# CLKB_SMI_if_1_6.net
KiCad netlist of a schematic drawn in Altium Designer
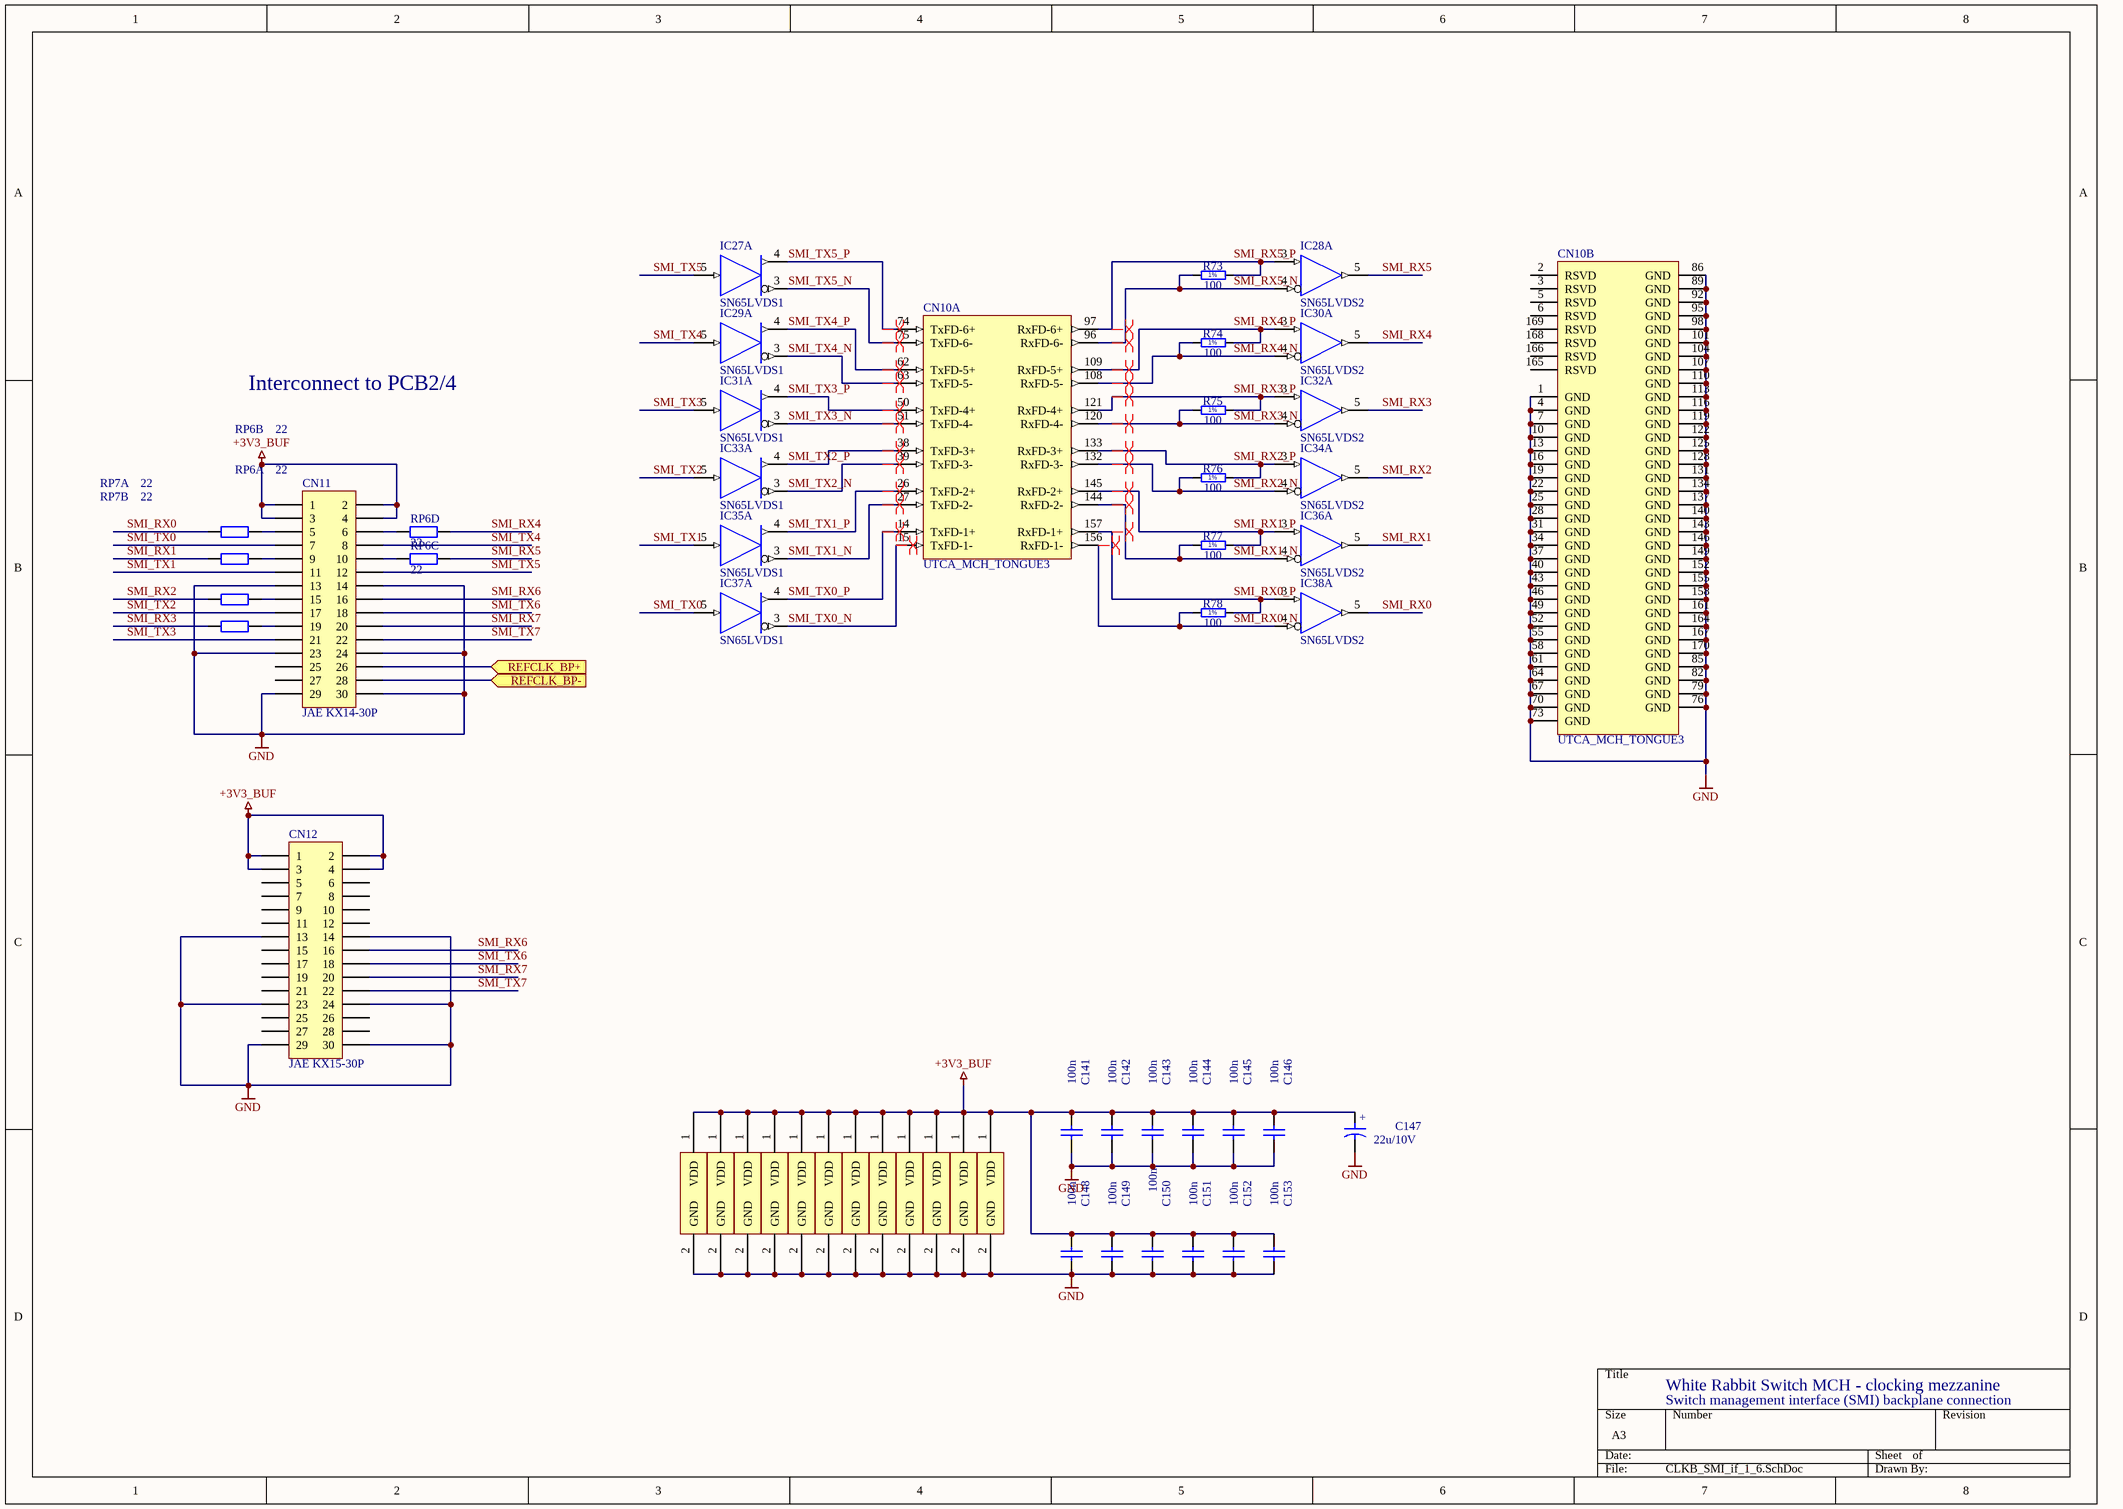
[diagram p0: CLKB_SMI_if_1_6.SchDoc]

(export (version "E")
  (design (tool "Eeschema 10.0.6"))
  (components
    (comp (ref "C141")
      (value "100n")
      (footprint "CAPC1608X87N")
      (description "Non-polarised capacitor")
      (fields
        (field (name "PART NUMBER") "CC0603_100NF_50V_10%_X7R")
        (field (name "VOLTAGE") "50V")
        (field (name "AUTHOR") "CERN DEM JLC")
      )
      (libsource (lib "Capacitors") (part "Capacitor - non polarized"))
    )
    (comp (ref "C142")
      (value "100n")
      (footprint "CAPC1608X87N")
      (description "Non-polarised capacitor")
      (fields
        (field (name "PART NUMBER") "CC0603_100NF_50V_10%_X7R")
        (field (name "VOLTAGE") "50V")
        (field (name "AUTHOR") "CERN DEM JLC")
      )
      (libsource (lib "Capacitors") (part "Capacitor - non polarized"))
    )
    (comp (ref "C143")
      (value "100n")
      (footprint "CAPC1608X87N")
      (description "Non-polarised capacitor")
      (fields
        (field (name "PART NUMBER") "CC0603_100NF_50V_10%_X7R")
        (field (name "VOLTAGE") "50V")
        (field (name "AUTHOR") "CERN DEM JLC")
      )
      (libsource (lib "Capacitors") (part "Capacitor - non polarized"))
    )
    (comp (ref "C144")
      (value "100n")
      (footprint "CAPC1608X87N")
      (description "Non-polarised capacitor")
      (fields
        (field (name "PART NUMBER") "CC0603_100NF_50V_10%_X7R")
        (field (name "VOLTAGE") "50V")
        (field (name "AUTHOR") "CERN DEM JLC")
      )
      (libsource (lib "Capacitors") (part "Capacitor - non polarized"))
    )
    (comp (ref "C145")
      (value "100n")
      (footprint "CAPC1608X87N")
      (description "Non-polarised capacitor")
      (fields
        (field (name "PART NUMBER") "CC0603_100NF_50V_10%_X7R")
        (field (name "VOLTAGE") "50V")
        (field (name "AUTHOR") "CERN DEM JLC")
      )
      (libsource (lib "Capacitors") (part "Capacitor - non polarized"))
    )
    (comp (ref "C146")
      (value "100n")
      (footprint "CAPC1608X87N")
      (description "Non-polarised capacitor")
      (fields
        (field (name "PART NUMBER") "CC0603_100NF_50V_10%_X7R")
        (field (name "VOLTAGE") "50V")
        (field (name "AUTHOR") "CERN DEM JLC")
      )
      (libsource (lib "Capacitors") (part "Capacitor - non polarized"))
    )
    (comp (ref "C147")
      (value "22u/10V")
      (footprint "CAPMP3216X180N")
      (description "Polarised capacitor")
      (fields
        (field (name "PART NUMBER") "CTE3216-18_22UF_10V_10%")
        (field (name "VOLTAGE") "10V")
        (field (name "AUTHOR") "CERN DEM JLC")
      )
      (libsource (lib "Capacitors") (part "Capacitor - polarized"))
    )
    (comp (ref "C148")
      (value "100n")
      (footprint "CAPC1608X87N")
      (description "Non-polarised capacitor")
      (fields
        (field (name "PART NUMBER") "CC0603_100NF_50V_10%_X7R")
        (field (name "VOLTAGE") "50V")
        (field (name "AUTHOR") "CERN DEM JLC")
      )
      (libsource (lib "Capacitors") (part "Capacitor - non polarized"))
    )
    (comp (ref "C149")
      (value "100n")
      (footprint "CAPC1608X87N")
      (description "Non-polarised capacitor")
      (fields
        (field (name "PART NUMBER") "CC0603_100NF_50V_10%_X7R")
        (field (name "VOLTAGE") "50V")
        (field (name "AUTHOR") "CERN DEM JLC")
      )
      (libsource (lib "Capacitors") (part "Capacitor - non polarized"))
    )
    (comp (ref "C150")
      (value "100n")
      (footprint "CAPC1608X87N")
      (description "Non-polarised capacitor")
      (fields
        (field (name "PART NUMBER") "CC0603_100NF_50V_10%_X7R")
        (field (name "VOLTAGE") "50V")
        (field (name "AUTHOR") "CERN DEM JLC")
      )
      (libsource (lib "Capacitors") (part "Capacitor - non polarized"))
    )
    (comp (ref "C151")
      (value "100n")
      (footprint "CAPC1608X87N")
      (description "Non-polarised capacitor")
      (fields
        (field (name "PART NUMBER") "CC0603_100NF_50V_10%_X7R")
        (field (name "VOLTAGE") "50V")
        (field (name "AUTHOR") "CERN DEM JLC")
      )
      (libsource (lib "Capacitors") (part "Capacitor - non polarized"))
    )
    (comp (ref "C152")
      (value "100n")
      (footprint "CAPC1608X87N")
      (description "Non-polarised capacitor")
      (fields
        (field (name "PART NUMBER") "CC0603_100NF_50V_10%_X7R")
        (field (name "VOLTAGE") "50V")
        (field (name "AUTHOR") "CERN DEM JLC")
      )
      (libsource (lib "Capacitors") (part "Capacitor - non polarized"))
    )
    (comp (ref "C153")
      (value "100n")
      (footprint "CAPC1608X87N")
      (description "Non-polarised capacitor")
      (fields
        (field (name "PART NUMBER") "CC0603_100NF_50V_10%_X7R")
        (field (name "VOLTAGE") "50V")
        (field (name "AUTHOR") "CERN DEM JLC")
      )
      (libsource (lib "Capacitors") (part "Capacitor - non polarized"))
    )
    (comp (ref "CN10")
      (value "UTCA_MCH_TONGUE3")
      (footprint "UTCA_MCH_TONGUE2_3_4")
      (description "microTCA MTCA.0 standard MCH connector 3")
      (libsource (lib "wr_switch") (part "UTCA_MCH_TONGUE3"))
    )
    (comp (ref "CN11")
      (value "JAE KX14-30P")
      (footprint "JAE_KX15_30P")
      (description "multipin B2B connector (plug)")
      (libsource (lib "wr_switch") (part "KX14_30p"))
    )
    (comp (ref "CN12")
      (value "JAE KX15-30P")
      (footprint "JAE_KX14_30P")
      (description "multipin B2B connector (plug)")
      (libsource (lib "wr_switch") (part "KX15_30p"))
    )
    (comp (ref "IC27")
      (value "SN65LVDS1")
      (footprint "SOT23-5AL")
      (description "TTL->LVDS buffer")
      (libsource (lib "wr_switch") (part "SN65LVDS1"))
    )
    (comp (ref "IC28")
      (value "SN65LVDS2")
      (footprint "SOT23-5AL")
      (description "LVDS->TTL buffer")
      (libsource (lib "wr_switch") (part "SN65LVDS2"))
    )
    (comp (ref "IC29")
      (value "SN65LVDS1")
      (footprint "SOT23-5AL")
      (description "TTL->LVDS buffer")
      (libsource (lib "wr_switch") (part "SN65LVDS1"))
    )
    (comp (ref "IC30")
      (value "SN65LVDS2")
      (footprint "SOT23-5AL")
      (description "LVDS->TTL buffer")
      (libsource (lib "wr_switch") (part "SN65LVDS2"))
    )
    (comp (ref "IC31")
      (value "SN65LVDS1")
      (footprint "SOT23-5AL")
      (description "TTL->LVDS buffer")
      (libsource (lib "wr_switch") (part "SN65LVDS1"))
    )
    (comp (ref "IC32")
      (value "SN65LVDS2")
      (footprint "SOT23-5AL")
      (description "LVDS->TTL buffer")
      (libsource (lib "wr_switch") (part "SN65LVDS2"))
    )
    (comp (ref "IC33")
      (value "SN65LVDS1")
      (footprint "SOT23-5AL")
      (description "TTL->LVDS buffer")
      (libsource (lib "wr_switch") (part "SN65LVDS1"))
    )
    (comp (ref "IC34")
      (value "SN65LVDS2")
      (footprint "SOT23-5AL")
      (description "LVDS->TTL buffer")
      (libsource (lib "wr_switch") (part "SN65LVDS2"))
    )
    (comp (ref "IC35")
      (value "SN65LVDS1")
      (footprint "SOT23-5AL")
      (description "TTL->LVDS buffer")
      (libsource (lib "wr_switch") (part "SN65LVDS1"))
    )
    (comp (ref "IC36")
      (value "SN65LVDS2")
      (footprint "SOT23-5AL")
      (description "LVDS->TTL buffer")
      (libsource (lib "wr_switch") (part "SN65LVDS2"))
    )
    (comp (ref "IC37")
      (value "SN65LVDS1")
      (footprint "SOT23-5AL")
      (description "TTL->LVDS buffer")
      (libsource (lib "wr_switch") (part "SN65LVDS1"))
    )
    (comp (ref "IC38")
      (value "SN65LVDS2")
      (footprint "SOT23-5AL")
      (description "LVDS->TTL buffer")
      (libsource (lib "wr_switch") (part "SN65LVDS2"))
    )
    (comp (ref "R73")
      (value "100")
      (footprint "RESC1608X55N")
      (description "Resistor - 1%")
      (fields
        (field (name "PART NUMBER") "R0603_100R_1%_0.1W_100PPM")
        (field (name "POWER") "0.1W")
        (field (name "AUTHOR") "CERN DEM JLC")
      )
      (libsource (lib "Resistors") (part "Resistor - 1%"))
    )
    (comp (ref "R74")
      (value "100")
      (footprint "RESC1608X55N")
      (description "Resistor - 1%")
      (fields
        (field (name "PART NUMBER") "R0603_100R_1%_0.1W_100PPM")
        (field (name "POWER") "0.1W")
        (field (name "AUTHOR") "CERN DEM JLC")
      )
      (libsource (lib "Resistors") (part "Resistor - 1%"))
    )
    (comp (ref "R75")
      (value "100")
      (footprint "RESC1608X55N")
      (description "Resistor - 1%")
      (fields
        (field (name "PART NUMBER") "R0603_100R_1%_0.1W_100PPM")
        (field (name "POWER") "0.1W")
        (field (name "AUTHOR") "CERN DEM JLC")
      )
      (libsource (lib "Resistors") (part "Resistor - 1%"))
    )
    (comp (ref "R76")
      (value "100")
      (footprint "RESC1608X55N")
      (description "Resistor - 1%")
      (fields
        (field (name "PART NUMBER") "R0603_100R_1%_0.1W_100PPM")
        (field (name "POWER") "0.1W")
        (field (name "AUTHOR") "CERN DEM JLC")
      )
      (libsource (lib "Resistors") (part "Resistor - 1%"))
    )
    (comp (ref "R77")
      (value "100")
      (footprint "RESC1608X55N")
      (description "Resistor - 1%")
      (fields
        (field (name "PART NUMBER") "R0603_100R_1%_0.1W_100PPM")
        (field (name "POWER") "0.1W")
        (field (name "AUTHOR") "CERN DEM JLC")
      )
      (libsource (lib "Resistors") (part "Resistor - 1%"))
    )
    (comp (ref "R78")
      (value "100")
      (footprint "RESC1608X55N")
      (description "Resistor - 1%")
      (fields
        (field (name "PART NUMBER") "R0603_100R_1%_0.1W_100PPM")
        (field (name "POWER") "0.1W")
        (field (name "AUTHOR") "CERN DEM JLC")
      )
      (libsource (lib "Resistors") (part "Resistor - 1%"))
    )
    (comp (ref "RP6")
      (value "22")
      (footprint "YC124")
      (description "4-resistor pack")
      (fields (field (name "Comment") "RES_PACK"))
      (libsource (lib "wr_switch") (part "Res_Pack4_22R_YC124"))
    )
    (comp (ref "RP7")
      (value "22")
      (footprint "YC124")
      (description "4-resistor pack")
      (fields (field (name "Comment") "RES_PACK"))
      (libsource (lib "") (part "Res_Pack4_22R_YC124_1"))
    )
  )
  (nets
    (net (code "1") (name "+3V3_BUF") (class "Default")
      (node (ref "C141") (pin "1") (pinfunction "1_1") (pintype "passive"))
      (node (ref "C142") (pin "1") (pinfunction "1_1") (pintype "passive"))
      (node (ref "C143") (pin "1") (pinfunction "1_1") (pintype "passive"))
      (node (ref "C144") (pin "1") (pinfunction "1_1") (pintype "passive"))
      (node (ref "C145") (pin "1") (pinfunction "1_1") (pintype "passive"))
      (node (ref "C146") (pin "1") (pinfunction "1_1") (pintype "passive"))
      (node (ref "C147") (pin "1") (pinfunction "1_1") (pintype "passive"))
      (node (ref "C148") (pin "1") (pinfunction "1_1") (pintype "passive"))
      (node (ref "C149") (pin "1") (pinfunction "1_1") (pintype "passive"))
      (node (ref "C150") (pin "1") (pinfunction "1_1") (pintype "passive"))
      (node (ref "C151") (pin "1") (pinfunction "1_1") (pintype "passive"))
      (node (ref "C152") (pin "1") (pinfunction "1_1") (pintype "passive"))
      (node (ref "C153") (pin "1") (pinfunction "1_1") (pintype "passive"))
      (node (ref "CN11") (pin "1") (pinfunction "1_1") (pintype "passive"))
      (node (ref "CN11") (pin "2") (pinfunction "2_2") (pintype "passive"))
      (node (ref "CN11") (pin "3") (pinfunction "3_3") (pintype "passive"))
      (node (ref "CN11") (pin "4") (pinfunction "4_4") (pintype "passive"))
      (node (ref "CN12") (pin "1") (pinfunction "1_1") (pintype "passive"))
      (node (ref "CN12") (pin "2") (pinfunction "2_2") (pintype "passive"))
      (node (ref "CN12") (pin "3") (pinfunction "3_3") (pintype "passive"))
      (node (ref "CN12") (pin "4") (pinfunction "4_4") (pintype "passive"))
      (node (ref "IC27") (pin "1") (pinfunction "VDD_1") (pintype "passive"))
      (node (ref "IC28") (pin "1") (pinfunction "VDD_1") (pintype "passive"))
      (node (ref "IC29") (pin "1") (pinfunction "VDD_1") (pintype "passive"))
      (node (ref "IC30") (pin "1") (pinfunction "VDD_1") (pintype "passive"))
      (node (ref "IC31") (pin "1") (pinfunction "VDD_1") (pintype "passive"))
      (node (ref "IC32") (pin "1") (pinfunction "VDD_1") (pintype "passive"))
      (node (ref "IC33") (pin "1") (pinfunction "VDD_1") (pintype "passive"))
      (node (ref "IC34") (pin "1") (pinfunction "VDD_1") (pintype "passive"))
      (node (ref "IC35") (pin "1") (pinfunction "VDD_1") (pintype "passive"))
      (node (ref "IC36") (pin "1") (pinfunction "VDD_1") (pintype "passive"))
      (node (ref "IC37") (pin "1") (pinfunction "VDD_1") (pintype "passive"))
      (node (ref "IC38") (pin "1") (pinfunction "VDD_1") (pintype "passive"))
    )
    (net (code "2") (name "/REFCLK_BP+") (class "Default")
      (node (ref "CN11") (pin "26") (pinfunction "26_26") (pintype "passive"))
    )
    (net (code "3") (name "/REFCLK_BP-") (class "Default")
      (node (ref "CN11") (pin "28") (pinfunction "28_28") (pintype "passive"))
    )
    (net (code "4") (name "/SMI_RX0") (class "Default")
      (node (ref "IC38") (pin "5") (pinfunction "Q_5") (pintype "output"))
      (node (ref "RP6") (pin "2") (pinfunction "A_2") (pintype "passive"))
    )
    (net (code "5") (name "/SMI_RX0_N") (class "Default")
      (node (ref "CN10") (pin "156") (pinfunction "RxFD-1-_156") (pintype "output"))
      (node (ref "IC38") (pin "4") (pinfunction "/A_4") (pintype "input"))
      (node (ref "R78") (pin "1") (pinfunction "1_1") (pintype "passive"))
    )
    (net (code "6") (name "/SMI_RX0_P") (class "Default")
      (node (ref "CN10") (pin "157") (pinfunction "RxFD-1+_157") (pintype "output"))
      (node (ref "IC38") (pin "3") (pinfunction "A_3") (pintype "input"))
      (node (ref "R78") (pin "2") (pinfunction "2_2") (pintype "passive"))
    )
    (net (code "7") (name "/SMI_RX1") (class "Default")
      (node (ref "IC36") (pin "5") (pinfunction "Q_5") (pintype "output"))
      (node (ref "RP6") (pin "1") (pinfunction "A_1") (pintype "passive"))
    )
    (net (code "8") (name "/SMI_RX1_N") (class "Default")
      (node (ref "CN10") (pin "144") (pinfunction "RxFD-2-_144") (pintype "output"))
      (node (ref "IC36") (pin "4") (pinfunction "/A_4") (pintype "input"))
      (node (ref "R77") (pin "1") (pinfunction "1_1") (pintype "passive"))
    )
    (net (code "9") (name "/SMI_RX1_P") (class "Default")
      (node (ref "CN10") (pin "145") (pinfunction "RxFD-2+_145") (pintype "output"))
      (node (ref "IC36") (pin "3") (pinfunction "A_3") (pintype "input"))
      (node (ref "R77") (pin "2") (pinfunction "2_2") (pintype "passive"))
    )
    (net (code "10") (name "/SMI_RX2") (class "Default")
      (node (ref "IC34") (pin "5") (pinfunction "Q_5") (pintype "output"))
      (node (ref "RP7") (pin "2") (pinfunction "A_2") (pintype "passive"))
    )
    (net (code "11") (name "/SMI_RX2_N") (class "Default")
      (node (ref "CN10") (pin "132") (pinfunction "RxFD-3-_132") (pintype "output"))
      (node (ref "IC34") (pin "4") (pinfunction "/A_4") (pintype "input"))
      (node (ref "R76") (pin "1") (pinfunction "1_1") (pintype "passive"))
    )
    (net (code "12") (name "/SMI_RX2_P") (class "Default")
      (node (ref "CN10") (pin "133") (pinfunction "RxFD-3+_133") (pintype "output"))
      (node (ref "IC34") (pin "3") (pinfunction "A_3") (pintype "input"))
      (node (ref "R76") (pin "2") (pinfunction "2_2") (pintype "passive"))
    )
    (net (code "13") (name "/SMI_RX3") (class "Default")
      (node (ref "IC32") (pin "5") (pinfunction "Q_5") (pintype "output"))
      (node (ref "RP7") (pin "1") (pinfunction "A_1") (pintype "passive"))
    )
    (net (code "14") (name "/SMI_RX3_N") (class "Default")
      (node (ref "CN10") (pin "120") (pinfunction "RxFD-4-_120") (pintype "output"))
      (node (ref "IC32") (pin "4") (pinfunction "/A_4") (pintype "input"))
      (node (ref "R75") (pin "1") (pinfunction "1_1") (pintype "passive"))
    )
    (net (code "15") (name "/SMI_RX3_P") (class "Default")
      (node (ref "CN10") (pin "121") (pinfunction "RxFD-4+_121") (pintype "output"))
      (node (ref "IC32") (pin "3") (pinfunction "A_3") (pintype "input"))
      (node (ref "R75") (pin "2") (pinfunction "2_2") (pintype "passive"))
    )
    (net (code "16") (name "/SMI_RX4") (class "Default")
      (node (ref "IC30") (pin "5") (pinfunction "Q_5") (pintype "output"))
      (node (ref "RP6") (pin "4") (pinfunction "A_4") (pintype "passive"))
    )
    (net (code "17") (name "/SMI_RX4_N") (class "Default")
      (node (ref "CN10") (pin "108") (pinfunction "RxFD-5-_108") (pintype "output"))
      (node (ref "IC30") (pin "4") (pinfunction "/A_4") (pintype "input"))
      (node (ref "R74") (pin "1") (pinfunction "1_1") (pintype "passive"))
    )
    (net (code "18") (name "/SMI_RX4_P") (class "Default")
      (node (ref "CN10") (pin "109") (pinfunction "RxFD-5+_109") (pintype "output"))
      (node (ref "IC30") (pin "3") (pinfunction "A_3") (pintype "input"))
      (node (ref "R74") (pin "2") (pinfunction "2_2") (pintype "passive"))
    )
    (net (code "19") (name "/SMI_RX5") (class "Default")
      (node (ref "IC28") (pin "5") (pinfunction "Q_5") (pintype "output"))
      (node (ref "RP6") (pin "3") (pinfunction "A_3") (pintype "passive"))
    )
    (net (code "20") (name "/SMI_RX5_N") (class "Default")
      (node (ref "CN10") (pin "96") (pinfunction "RxFD-6-_96") (pintype "output"))
      (node (ref "IC28") (pin "4") (pinfunction "/A_4") (pintype "input"))
      (node (ref "R73") (pin "1") (pinfunction "1_1") (pintype "passive"))
    )
    (net (code "21") (name "/SMI_RX5_P") (class "Default")
      (node (ref "CN10") (pin "97") (pinfunction "RxFD-6+_97") (pintype "output"))
      (node (ref "IC28") (pin "3") (pinfunction "A_3") (pintype "input"))
      (node (ref "R73") (pin "2") (pinfunction "2_2") (pintype "passive"))
    )
    (net (code "22") (name "/SMI_RX6") (class "Default")
      (node (ref "CN11") (pin "16") (pinfunction "16_16") (pintype "passive"))
      (node (ref "CN12") (pin "16") (pinfunction "16_16") (pintype "passive"))
    )
    (net (code "23") (name "/SMI_RX7") (class "Default")
      (node (ref "CN11") (pin "20") (pinfunction "20_20") (pintype "passive"))
      (node (ref "CN12") (pin "20") (pinfunction "20_20") (pintype "passive"))
    )
    (net (code "24") (name "/SMI_TX0") (class "Default")
      (node (ref "CN11") (pin "7") (pinfunction "7_7") (pintype "passive"))
      (node (ref "IC37") (pin "5") (pinfunction "A_5") (pintype "input"))
    )
    (net (code "25") (name "/SMI_TX0_N") (class "Default")
      (node (ref "CN10") (pin "15") (pinfunction "TxFD-1-_15") (pintype "input"))
      (node (ref "IC37") (pin "3") (pinfunction "/Q_3") (pintype "output"))
    )
    (net (code "26") (name "/SMI_TX0_P") (class "Default")
      (node (ref "CN10") (pin "14") (pinfunction "TxFD-1+_14") (pintype "input"))
      (node (ref "IC37") (pin "4") (pinfunction "Q_4") (pintype "output"))
    )
    (net (code "27") (name "/SMI_TX1") (class "Default")
      (node (ref "CN11") (pin "11") (pinfunction "11_11") (pintype "passive"))
      (node (ref "IC35") (pin "5") (pinfunction "A_5") (pintype "input"))
    )
    (net (code "28") (name "/SMI_TX1_N") (class "Default")
      (node (ref "CN10") (pin "27") (pinfunction "TxFD-2-_27") (pintype "input"))
      (node (ref "IC35") (pin "3") (pinfunction "/Q_3") (pintype "output"))
    )
    (net (code "29") (name "/SMI_TX1_P") (class "Default")
      (node (ref "CN10") (pin "26") (pinfunction "TxFD-2+_26") (pintype "input"))
      (node (ref "IC35") (pin "4") (pinfunction "Q_4") (pintype "output"))
    )
    (net (code "30") (name "/SMI_TX2") (class "Default")
      (node (ref "CN11") (pin "17") (pinfunction "17_17") (pintype "passive"))
      (node (ref "IC33") (pin "5") (pinfunction "A_5") (pintype "input"))
    )
    (net (code "31") (name "/SMI_TX2_N") (class "Default")
      (node (ref "CN10") (pin "39") (pinfunction "TxFD-3-_39") (pintype "input"))
      (node (ref "IC33") (pin "3") (pinfunction "/Q_3") (pintype "output"))
    )
    (net (code "32") (name "/SMI_TX2_P") (class "Default")
      (node (ref "CN10") (pin "38") (pinfunction "TxFD-3+_38") (pintype "input"))
      (node (ref "IC33") (pin "4") (pinfunction "Q_4") (pintype "output"))
    )
    (net (code "33") (name "/SMI_TX3") (class "Default")
      (node (ref "CN11") (pin "21") (pinfunction "21_21") (pintype "passive"))
      (node (ref "IC31") (pin "5") (pinfunction "A_5") (pintype "input"))
    )
    (net (code "34") (name "/SMI_TX3_N") (class "Default")
      (node (ref "CN10") (pin "51") (pinfunction "TxFD-4-_51") (pintype "input"))
      (node (ref "IC31") (pin "3") (pinfunction "/Q_3") (pintype "output"))
    )
    (net (code "35") (name "/SMI_TX3_P") (class "Default")
      (node (ref "CN10") (pin "50") (pinfunction "TxFD-4+_50") (pintype "input"))
      (node (ref "IC31") (pin "4") (pinfunction "Q_4") (pintype "output"))
    )
    (net (code "36") (name "/SMI_TX4") (class "Default")
      (node (ref "CN11") (pin "8") (pinfunction "8_8") (pintype "passive"))
      (node (ref "IC29") (pin "5") (pinfunction "A_5") (pintype "input"))
    )
    (net (code "37") (name "/SMI_TX4_N") (class "Default")
      (node (ref "CN10") (pin "63") (pinfunction "TxFD-5-_63") (pintype "input"))
      (node (ref "IC29") (pin "3") (pinfunction "/Q_3") (pintype "output"))
    )
    (net (code "38") (name "/SMI_TX4_P") (class "Default")
      (node (ref "CN10") (pin "62") (pinfunction "TxFD-5+_62") (pintype "input"))
      (node (ref "IC29") (pin "4") (pinfunction "Q_4") (pintype "output"))
    )
    (net (code "39") (name "/SMI_TX5") (class "Default")
      (node (ref "CN11") (pin "12") (pinfunction "12_12") (pintype "passive"))
      (node (ref "IC27") (pin "5") (pinfunction "A_5") (pintype "input"))
    )
    (net (code "40") (name "/SMI_TX5_N") (class "Default")
      (node (ref "CN10") (pin "75") (pinfunction "TxFD-6-_75") (pintype "input"))
      (node (ref "IC27") (pin "3") (pinfunction "/Q_3") (pintype "output"))
    )
    (net (code "41") (name "/SMI_TX5_P") (class "Default")
      (node (ref "CN10") (pin "74") (pinfunction "TxFD-6+_74") (pintype "input"))
      (node (ref "IC27") (pin "4") (pinfunction "Q_4") (pintype "output"))
    )
    (net (code "42") (name "/SMI_TX6") (class "Default")
      (node (ref "CN11") (pin "18") (pinfunction "18_18") (pintype "passive"))
      (node (ref "CN12") (pin "18") (pinfunction "18_18") (pintype "passive"))
    )
    (net (code "43") (name "/SMI_TX7") (class "Default")
      (node (ref "CN11") (pin "22") (pinfunction "22_22") (pintype "passive"))
      (node (ref "CN12") (pin "22") (pinfunction "22_22") (pintype "passive"))
    )
    (net (code "44") (name "GND") (class "Default")
      (node (ref "C141") (pin "2") (pinfunction "2_2") (pintype "passive"))
      (node (ref "C142") (pin "2") (pinfunction "2_2") (pintype "passive"))
      (node (ref "C143") (pin "2") (pinfunction "2_2") (pintype "passive"))
      (node (ref "C144") (pin "2") (pinfunction "2_2") (pintype "passive"))
      (node (ref "C145") (pin "2") (pinfunction "2_2") (pintype "passive"))
      (node (ref "C146") (pin "2") (pinfunction "2_2") (pintype "passive"))
      (node (ref "C147") (pin "2") (pinfunction "2_2") (pintype "passive"))
      (node (ref "C148") (pin "2") (pinfunction "2_2") (pintype "passive"))
      (node (ref "C149") (pin "2") (pinfunction "2_2") (pintype "passive"))
      (node (ref "C150") (pin "2") (pinfunction "2_2") (pintype "passive"))
      (node (ref "C151") (pin "2") (pinfunction "2_2") (pintype "passive"))
      (node (ref "C152") (pin "2") (pinfunction "2_2") (pintype "passive"))
      (node (ref "C153") (pin "2") (pinfunction "2_2") (pintype "passive"))
      (node (ref "CN10") (pin "1") (pinfunction "GND_1") (pintype "power_in"))
      (node (ref "CN10") (pin "10") (pinfunction "GND_10") (pintype "power_in"))
      (node (ref "CN10") (pin "101") (pinfunction "GND_101") (pintype "power_in"))
      (node (ref "CN10") (pin "104") (pinfunction "GND_104") (pintype "power_in"))
      (node (ref "CN10") (pin "107") (pinfunction "GND_107") (pintype "power_in"))
      (node (ref "CN10") (pin "110") (pinfunction "GND_110") (pintype "power_in"))
      (node (ref "CN10") (pin "113") (pinfunction "GND_113") (pintype "power_in"))
      (node (ref "CN10") (pin "116") (pinfunction "GND_116") (pintype "power_in"))
      (node (ref "CN10") (pin "119") (pinfunction "GND_119") (pintype "power_in"))
      (node (ref "CN10") (pin "122") (pinfunction "GND_122") (pintype "power_in"))
      (node (ref "CN10") (pin "125") (pinfunction "GND_125") (pintype "power_in"))
      (node (ref "CN10") (pin "128") (pinfunction "GND_128") (pintype "power_in"))
      (node (ref "CN10") (pin "13") (pinfunction "GND_13") (pintype "power_in"))
      (node (ref "CN10") (pin "131") (pinfunction "GND_131") (pintype "power_in"))
      (node (ref "CN10") (pin "134") (pinfunction "GND_134") (pintype "power_in"))
      (node (ref "CN10") (pin "137") (pinfunction "GND_137") (pintype "power_in"))
      (node (ref "CN10") (pin "140") (pinfunction "GND_140") (pintype "power_in"))
      (node (ref "CN10") (pin "143") (pinfunction "GND_143") (pintype "power_in"))
      (node (ref "CN10") (pin "146") (pinfunction "GND_146") (pintype "power_in"))
      (node (ref "CN10") (pin "149") (pinfunction "GND_149") (pintype "power_in"))
      (node (ref "CN10") (pin "152") (pinfunction "GND_152") (pintype "power_in"))
      (node (ref "CN10") (pin "155") (pinfunction "GND_155") (pintype "power_in"))
      (node (ref "CN10") (pin "158") (pinfunction "GND_158") (pintype "power_in"))
      (node (ref "CN10") (pin "16") (pinfunction "GND_16") (pintype "power_in"))
      (node (ref "CN10") (pin "161") (pinfunction "GND_161") (pintype "power_in"))
      (node (ref "CN10") (pin "164") (pinfunction "GND_164") (pintype "power_in"))
      (node (ref "CN10") (pin "167") (pinfunction "GND_167") (pintype "power_in"))
      (node (ref "CN10") (pin "170") (pinfunction "GND_170") (pintype "power_in"))
      (node (ref "CN10") (pin "19") (pinfunction "GND_19") (pintype "power_in"))
      (node (ref "CN10") (pin "22") (pinfunction "GND_22") (pintype "power_in"))
      (node (ref "CN10") (pin "25") (pinfunction "GND_25") (pintype "power_in"))
      (node (ref "CN10") (pin "28") (pinfunction "GND_28") (pintype "power_in"))
      (node (ref "CN10") (pin "31") (pinfunction "GND_31") (pintype "power_in"))
      (node (ref "CN10") (pin "34") (pinfunction "GND_34") (pintype "power_in"))
      (node (ref "CN10") (pin "37") (pinfunction "GND_37") (pintype "power_in"))
      (node (ref "CN10") (pin "4") (pinfunction "GND_4") (pintype "power_in"))
      (node (ref "CN10") (pin "40") (pinfunction "GND_40") (pintype "power_in"))
      (node (ref "CN10") (pin "43") (pinfunction "GND_43") (pintype "power_in"))
      (node (ref "CN10") (pin "46") (pinfunction "GND_46") (pintype "power_in"))
      (node (ref "CN10") (pin "49") (pinfunction "GND_49") (pintype "power_in"))
      (node (ref "CN10") (pin "52") (pinfunction "GND_52") (pintype "power_in"))
      (node (ref "CN10") (pin "55") (pinfunction "GND_55") (pintype "power_in"))
      (node (ref "CN10") (pin "58") (pinfunction "GND_58") (pintype "power_in"))
      (node (ref "CN10") (pin "61") (pinfunction "GND_61") (pintype "power_in"))
      (node (ref "CN10") (pin "64") (pinfunction "GND_64") (pintype "power_in"))
      (node (ref "CN10") (pin "67") (pinfunction "GND_67") (pintype "power_in"))
      (node (ref "CN10") (pin "7") (pinfunction "GND_7") (pintype "power_in"))
      (node (ref "CN10") (pin "70") (pinfunction "GND_70") (pintype "power_in"))
      (node (ref "CN10") (pin "73") (pinfunction "GND_73") (pintype "power_in"))
      (node (ref "CN10") (pin "76") (pinfunction "GND_76") (pintype "power_in"))
      (node (ref "CN10") (pin "79") (pinfunction "GND_79") (pintype "power_in"))
      (node (ref "CN10") (pin "82") (pinfunction "GND_82") (pintype "power_in"))
      (node (ref "CN10") (pin "85") (pinfunction "GND_85") (pintype "power_in"))
      (node (ref "CN10") (pin "86") (pinfunction "GND_86") (pintype "power_in"))
      (node (ref "CN10") (pin "89") (pinfunction "GND_89") (pintype "power_in"))
      (node (ref "CN10") (pin "92") (pinfunction "GND_92") (pintype "power_in"))
      (node (ref "CN10") (pin "95") (pinfunction "GND_95") (pintype "power_in"))
      (node (ref "CN10") (pin "98") (pinfunction "GND_98") (pintype "power_in"))
      (node (ref "CN11") (pin "13") (pinfunction "13_13") (pintype "passive"))
      (node (ref "CN11") (pin "14") (pinfunction "14_14") (pintype "passive"))
      (node (ref "CN11") (pin "23") (pinfunction "23_23") (pintype "passive"))
      (node (ref "CN11") (pin "24") (pinfunction "24_24") (pintype "passive"))
      (node (ref "CN11") (pin "29") (pinfunction "29_29") (pintype "passive"))
      (node (ref "CN11") (pin "30") (pinfunction "30_30") (pintype "passive"))
      (node (ref "CN12") (pin "13") (pinfunction "13_13") (pintype "passive"))
      (node (ref "CN12") (pin "14") (pinfunction "14_14") (pintype "passive"))
      (node (ref "CN12") (pin "23") (pinfunction "23_23") (pintype "passive"))
      (node (ref "CN12") (pin "24") (pinfunction "24_24") (pintype "passive"))
      (node (ref "CN12") (pin "29") (pinfunction "29_29") (pintype "passive"))
      (node (ref "CN12") (pin "30") (pinfunction "30_30") (pintype "passive"))
      (node (ref "IC27") (pin "2") (pinfunction "GND_2") (pintype "passive"))
      (node (ref "IC28") (pin "2") (pinfunction "GND_2") (pintype "passive"))
      (node (ref "IC29") (pin "2") (pinfunction "GND_2") (pintype "passive"))
      (node (ref "IC30") (pin "2") (pinfunction "GND_2") (pintype "passive"))
      (node (ref "IC31") (pin "2") (pinfunction "GND_2") (pintype "passive"))
      (node (ref "IC32") (pin "2") (pinfunction "GND_2") (pintype "passive"))
      (node (ref "IC33") (pin "2") (pinfunction "GND_2") (pintype "passive"))
      (node (ref "IC34") (pin "2") (pinfunction "GND_2") (pintype "passive"))
      (node (ref "IC35") (pin "2") (pinfunction "GND_2") (pintype "passive"))
      (node (ref "IC36") (pin "2") (pinfunction "GND_2") (pintype "passive"))
      (node (ref "IC37") (pin "2") (pinfunction "GND_2") (pintype "passive"))
      (node (ref "IC38") (pin "2") (pinfunction "GND_2") (pintype "passive"))
    )
    (net (code "45") (name "Net-(RP6A-B)") (class "Default")
      (node (ref "CN11") (pin "9") (pinfunction "9_9") (pintype "passive"))
      (node (ref "RP6") (pin "8") (pinfunction "B_8") (pintype "passive"))
    )
    (net (code "46") (name "Net-(RP6B-B)") (class "Default")
      (node (ref "CN11") (pin "5") (pinfunction "5_5") (pintype "passive"))
      (node (ref "RP6") (pin "7") (pinfunction "B_7") (pintype "passive"))
    )
    (net (code "47") (name "Net-(RP6C-B)") (class "Default")
      (node (ref "CN11") (pin "10") (pinfunction "10_10") (pintype "passive"))
      (node (ref "RP6") (pin "6") (pinfunction "B_6") (pintype "passive"))
    )
    (net (code "48") (name "Net-(RP6D-B)") (class "Default")
      (node (ref "CN11") (pin "6") (pinfunction "6_6") (pintype "passive"))
      (node (ref "RP6") (pin "5") (pinfunction "B_5") (pintype "passive"))
    )
    (net (code "49") (name "Net-(RP7A-B)") (class "Default")
      (node (ref "CN11") (pin "19") (pinfunction "19_19") (pintype "passive"))
      (node (ref "RP7") (pin "8") (pinfunction "B_8") (pintype "passive"))
    )
    (net (code "50") (name "Net-(RP7B-B)") (class "Default")
      (node (ref "CN11") (pin "15") (pinfunction "15_15") (pintype "passive"))
      (node (ref "RP7") (pin "7") (pinfunction "B_7") (pintype "passive"))
    )
    (net (code "51") (name "unconnected-(CN10B-RSVD-Pad2)") (class "Default")
      (node (ref "CN10") (pin "2") (pinfunction "RSVD_2") (pintype "passive"))
    )
    (net (code "52") (name "unconnected-(CN10B-RSVD-Pad3)") (class "Default")
      (node (ref "CN10") (pin "3") (pinfunction "RSVD_3") (pintype "passive"))
    )
    (net (code "53") (name "unconnected-(CN10B-RSVD-Pad5)") (class "Default")
      (node (ref "CN10") (pin "5") (pinfunction "RSVD_5") (pintype "passive"))
    )
    (net (code "54") (name "unconnected-(CN10B-RSVD-Pad6)") (class "Default")
      (node (ref "CN10") (pin "6") (pinfunction "RSVD_6") (pintype "passive"))
    )
    (net (code "55") (name "unconnected-(CN10B-RSVD-Pad165)") (class "Default")
      (node (ref "CN10") (pin "165") (pinfunction "RSVD_165") (pintype "passive"))
    )
    (net (code "56") (name "unconnected-(CN10B-RSVD-Pad166)") (class "Default")
      (node (ref "CN10") (pin "166") (pinfunction "RSVD_166") (pintype "passive"))
    )
    (net (code "57") (name "unconnected-(CN10B-RSVD-Pad168)") (class "Default")
      (node (ref "CN10") (pin "168") (pinfunction "RSVD_168") (pintype "passive"))
    )
    (net (code "58") (name "unconnected-(CN10B-RSVD-Pad169)") (class "Default")
      (node (ref "CN10") (pin "169") (pinfunction "RSVD_169") (pintype "passive"))
    )
    (net (code "59") (name "unconnected-(CN11-Pad25)") (class "Default")
      (node (ref "CN11") (pin "25") (pinfunction "25_25") (pintype "passive"))
    )
    (net (code "60") (name "unconnected-(CN11-Pad27)") (class "Default")
      (node (ref "CN11") (pin "27") (pinfunction "27_27") (pintype "passive"))
    )
    (net (code "61") (name "unconnected-(CN12-Pad5)") (class "Default")
      (node (ref "CN12") (pin "5") (pinfunction "5_5") (pintype "passive"))
    )
    (net (code "62") (name "unconnected-(CN12-Pad6)") (class "Default")
      (node (ref "CN12") (pin "6") (pinfunction "6_6") (pintype "passive"))
    )
    (net (code "63") (name "unconnected-(CN12-Pad7)") (class "Default")
      (node (ref "CN12") (pin "7") (pinfunction "7_7") (pintype "passive"))
    )
    (net (code "64") (name "unconnected-(CN12-Pad8)") (class "Default")
      (node (ref "CN12") (pin "8") (pinfunction "8_8") (pintype "passive"))
    )
    (net (code "65") (name "unconnected-(CN12-Pad9)") (class "Default")
      (node (ref "CN12") (pin "9") (pinfunction "9_9") (pintype "passive"))
    )
    (net (code "66") (name "unconnected-(CN12-Pad10)") (class "Default")
      (node (ref "CN12") (pin "10") (pinfunction "10_10") (pintype "passive"))
    )
    (net (code "67") (name "unconnected-(CN12-Pad11)") (class "Default")
      (node (ref "CN12") (pin "11") (pinfunction "11_11") (pintype "passive"))
    )
    (net (code "68") (name "unconnected-(CN12-Pad12)") (class "Default")
      (node (ref "CN12") (pin "12") (pinfunction "12_12") (pintype "passive"))
    )
    (net (code "69") (name "unconnected-(CN12-Pad15)") (class "Default")
      (node (ref "CN12") (pin "15") (pinfunction "15_15") (pintype "passive"))
    )
    (net (code "70") (name "unconnected-(CN12-Pad17)") (class "Default")
      (node (ref "CN12") (pin "17") (pinfunction "17_17") (pintype "passive"))
    )
    (net (code "71") (name "unconnected-(CN12-Pad19)") (class "Default")
      (node (ref "CN12") (pin "19") (pinfunction "19_19") (pintype "passive"))
    )
    (net (code "72") (name "unconnected-(CN12-Pad21)") (class "Default")
      (node (ref "CN12") (pin "21") (pinfunction "21_21") (pintype "passive"))
    )
    (net (code "73") (name "unconnected-(CN12-Pad25)") (class "Default")
      (node (ref "CN12") (pin "25") (pinfunction "25_25") (pintype "passive"))
    )
    (net (code "74") (name "unconnected-(CN12-Pad26)") (class "Default")
      (node (ref "CN12") (pin "26") (pinfunction "26_26") (pintype "passive"))
    )
    (net (code "75") (name "unconnected-(CN12-Pad27)") (class "Default")
      (node (ref "CN12") (pin "27") (pinfunction "27_27") (pintype "passive"))
    )
    (net (code "76") (name "unconnected-(CN12-Pad28)") (class "Default")
      (node (ref "CN12") (pin "28") (pinfunction "28_28") (pintype "passive"))
    )
  )
)
